# Guide_laser.net
KiCad netlist of a schematic drawn in Altium Designer
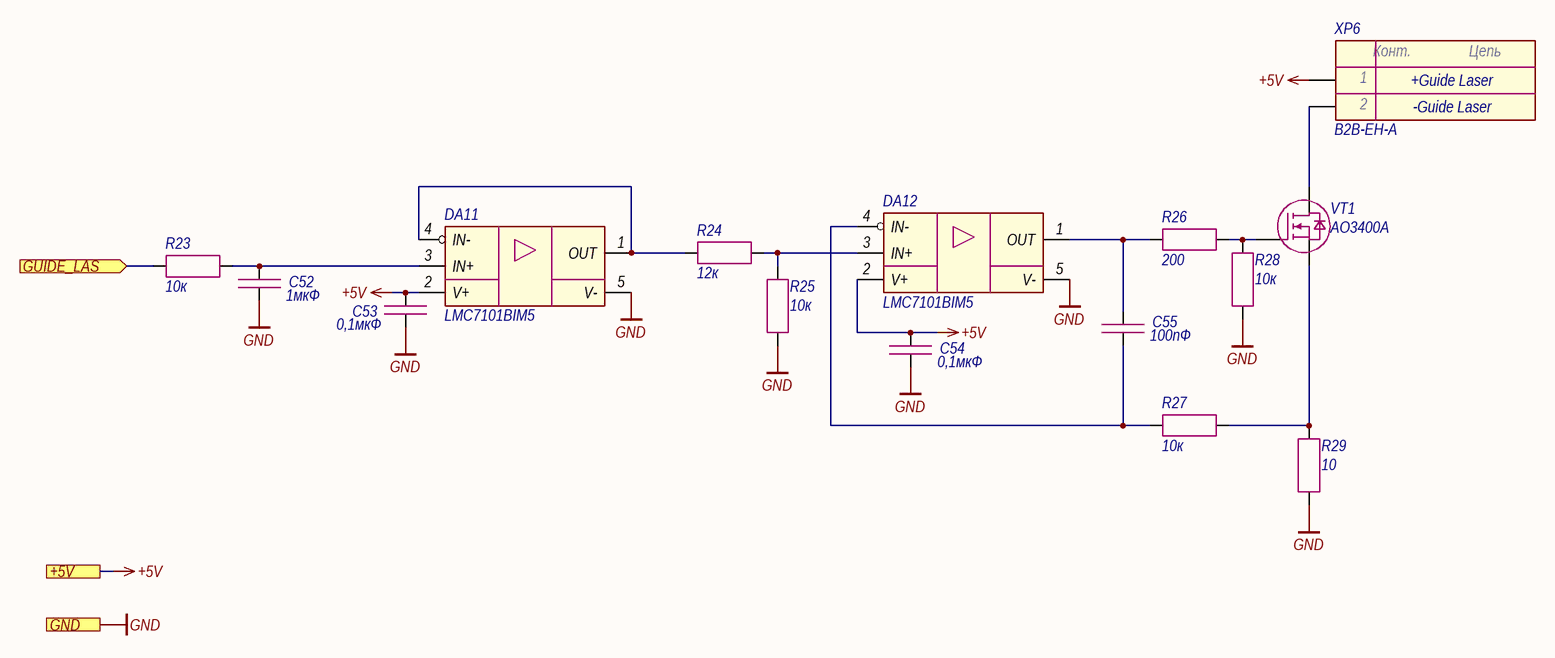
[diagram p0: Guide_laser.SchDoc]

(export (version "E")
  (design (tool "Eeschema 10.0.6"))
  (components
    (comp (ref "C52")
      (value "1мкФ")
      (footprint "Pcb_library:CAP_0603")
      (fields (field (name "MANUFACTURER") "Murata"))
      (libsource (lib "Schem_library") (part "Capacitor"))
    )
    (comp (ref "C53")
      (value "0,1мкФ")
      (footprint "Pcb_library:CAP_0603")
      (fields (field (name "MANUFACTURER") "Murata"))
      (libsource (lib "Schem_library") (part "Capacitor"))
    )
    (comp (ref "C54")
      (value "0,1мкФ")
      (footprint "Pcb_library:CAP_0603")
      (fields (field (name "MANUFACTURER") "Murata"))
      (libsource (lib "Schem_library") (part "Capacitor"))
    )
    (comp (ref "C55")
      (value "100пФ")
      (footprint "Pcb_library:CAP_0603")
      (fields (field (name "MANUFACTURER") "Murata"))
      (libsource (lib "Schem_library") (part "Capacitor"))
    )
    (comp (ref "DA11")
      (value "LMC7101BIM5")
      (footprint "Pcb_library:SOT-23-5")
      (fields (field (name "MANUFACTURER") "Texas Instruments"))
      (libsource (lib "Schem_library") (part "LMC7101"))
    )
    (comp (ref "DA12")
      (value "LMC7101BIM5")
      (footprint "Pcb_library:SOT-23-5")
      (fields (field (name "MANUFACTURER") "Texas Instruments"))
      (libsource (lib "Schem_library") (part "LMC7101"))
    )
    (comp (ref "R23")
      (value "10к")
      (footprint "Pcb_library:RES_0603")
      (fields (field (name "MANUFACTURER") "Yageo"))
      (libsource (lib "Schem_library") (part "Resistor"))
    )
    (comp (ref "R24")
      (value "12к")
      (footprint "Pcb_library:RES_0603")
      (fields (field (name "MANUFACTURER") "Yageo"))
      (libsource (lib "Schem_library") (part "Resistor"))
    )
    (comp (ref "R25")
      (value "10к")
      (footprint "Pcb_library:RES_0603")
      (fields (field (name "MANUFACTURER") "Yageo"))
      (libsource (lib "Schem_library") (part "Resistor"))
    )
    (comp (ref "R26")
      (value "200")
      (footprint "Pcb_library:RES_0603")
      (fields (field (name "MANUFACTURER") "Yageo"))
      (libsource (lib "Schem_library") (part "Resistor"))
    )
    (comp (ref "R27")
      (value "10к")
      (footprint "Pcb_library:RES_0603")
      (fields (field (name "MANUFACTURER") "Yageo"))
      (libsource (lib "Schem_library") (part "Resistor"))
    )
    (comp (ref "R28")
      (value "10к")
      (footprint "Pcb_library:RES_0603")
      (fields (field (name "MANUFACTURER") "Yageo"))
      (libsource (lib "Schem_library") (part "Resistor"))
    )
    (comp (ref "R29")
      (value "10")
      (footprint "Pcb_library:RES_1210")
      (fields (field (name "MANUFACTURER") "Yageo"))
      (libsource (lib "Schem_library") (part "Resistor"))
    )
    (comp (ref "VT1")
      (value "AO3400A")
      (footprint "Pcb_library:SOT-23-3")
      (fields (field (name "MANUFACTURER") "UMW"))
      (libsource (lib "Schem_library") (part "MOSFET N-channel"))
    )
    (comp (ref "XP6")
      (value "B2B-EH-A")
      (footprint "Pcb_library:B2B-EH-A")
      (fields (field (name "MANUFACTURER") "JST"))
      (libsource (lib "Schem_library") (part "Connector-2"))
    )
  )
  (nets
    (net (code "1") (name "+5V") (class "Default")
      (node (ref "C53") (pin "1") (pinfunction "1_1") (pintype "passive"))
      (node (ref "C54") (pin "1") (pinfunction "1_1") (pintype "passive"))
      (node (ref "DA11") (pin "2") (pinfunction "V+_2") (pintype "passive"))
      (node (ref "DA12") (pin "2") (pinfunction "V+_2") (pintype "passive"))
      (node (ref "XP6") (pin "1") (pintype "passive"))
    )
    (net (code "2") (name "/GUIDE_LAS") (class "Default")
      (node (ref "R23") (pin "1") (pinfunction "1_1") (pintype "passive"))
    )
    (net (code "3") (name "GND") (class "Default")
      (node (ref "C52") (pin "2") (pinfunction "2_2") (pintype "passive"))
      (node (ref "C53") (pin "2") (pinfunction "2_2") (pintype "passive"))
      (node (ref "C54") (pin "2") (pinfunction "2_2") (pintype "passive"))
      (node (ref "DA11") (pin "5") (pinfunction "V-_5") (pintype "passive"))
      (node (ref "DA12") (pin "5") (pinfunction "V-_5") (pintype "passive"))
      (node (ref "R25") (pin "2") (pinfunction "2_2") (pintype "passive"))
      (node (ref "R28") (pin "1") (pinfunction "1_1") (pintype "passive"))
      (node (ref "R29") (pin "1") (pinfunction "1_1") (pintype "passive"))
    )
    (net (code "4") (name "Net-(DA11-IN+)") (class "Default")
      (node (ref "C52") (pin "1") (pinfunction "1_1") (pintype "passive"))
      (node (ref "DA11") (pin "3") (pinfunction "IN+_3") (pintype "passive"))
      (node (ref "R23") (pin "2") (pinfunction "2_2") (pintype "passive"))
    )
    (net (code "5") (name "Net-(DA11-IN-)") (class "Default")
      (node (ref "DA11") (pin "1") (pinfunction "OUT_1") (pintype "passive"))
      (node (ref "DA11") (pin "4") (pinfunction "IN-_4") (pintype "passive"))
      (node (ref "R24") (pin "1") (pinfunction "1_1") (pintype "passive"))
    )
    (net (code "6") (name "Net-(DA12-IN+)") (class "Default")
      (node (ref "DA12") (pin "3") (pinfunction "IN+_3") (pintype "passive"))
      (node (ref "R24") (pin "2") (pinfunction "2_2") (pintype "passive"))
      (node (ref "R25") (pin "1") (pinfunction "1_1") (pintype "passive"))
    )
    (net (code "7") (name "Net-(DA12-IN-)") (class "Default")
      (node (ref "C55") (pin "2") (pinfunction "2_2") (pintype "passive"))
      (node (ref "DA12") (pin "4") (pinfunction "IN-_4") (pintype "passive"))
      (node (ref "R27") (pin "1") (pinfunction "1_1") (pintype "passive"))
    )
    (net (code "8") (name "Net-(DA12-OUT)") (class "Default")
      (node (ref "C55") (pin "1") (pinfunction "1_1") (pintype "passive"))
      (node (ref "DA12") (pin "1") (pinfunction "OUT_1") (pintype "passive"))
      (node (ref "R26") (pin "1") (pinfunction "1_1") (pintype "passive"))
    )
    (net (code "9") (name "Net-(VT1-D)") (class "Default")
      (node (ref "VT1") (pin "3") (pinfunction "D_3") (pintype "passive"))
      (node (ref "XP6") (pin "2") (pintype "passive"))
    )
    (net (code "10") (name "Net-(VT1-G)") (class "Default")
      (node (ref "R26") (pin "2") (pinfunction "2_2") (pintype "passive"))
      (node (ref "R28") (pin "2") (pinfunction "2_2") (pintype "passive"))
      (node (ref "VT1") (pin "1") (pinfunction "G_1") (pintype "passive"))
    )
    (net (code "11") (name "Net-(VT1-S)") (class "Default")
      (node (ref "R27") (pin "2") (pinfunction "2_2") (pintype "passive"))
      (node (ref "R29") (pin "2") (pinfunction "2_2") (pintype "passive"))
      (node (ref "VT1") (pin "2") (pinfunction "S_2") (pintype "passive"))
    )
  )
)
